# Componentes.net
KiCad netlist of a schematic drawn in Altium Designer
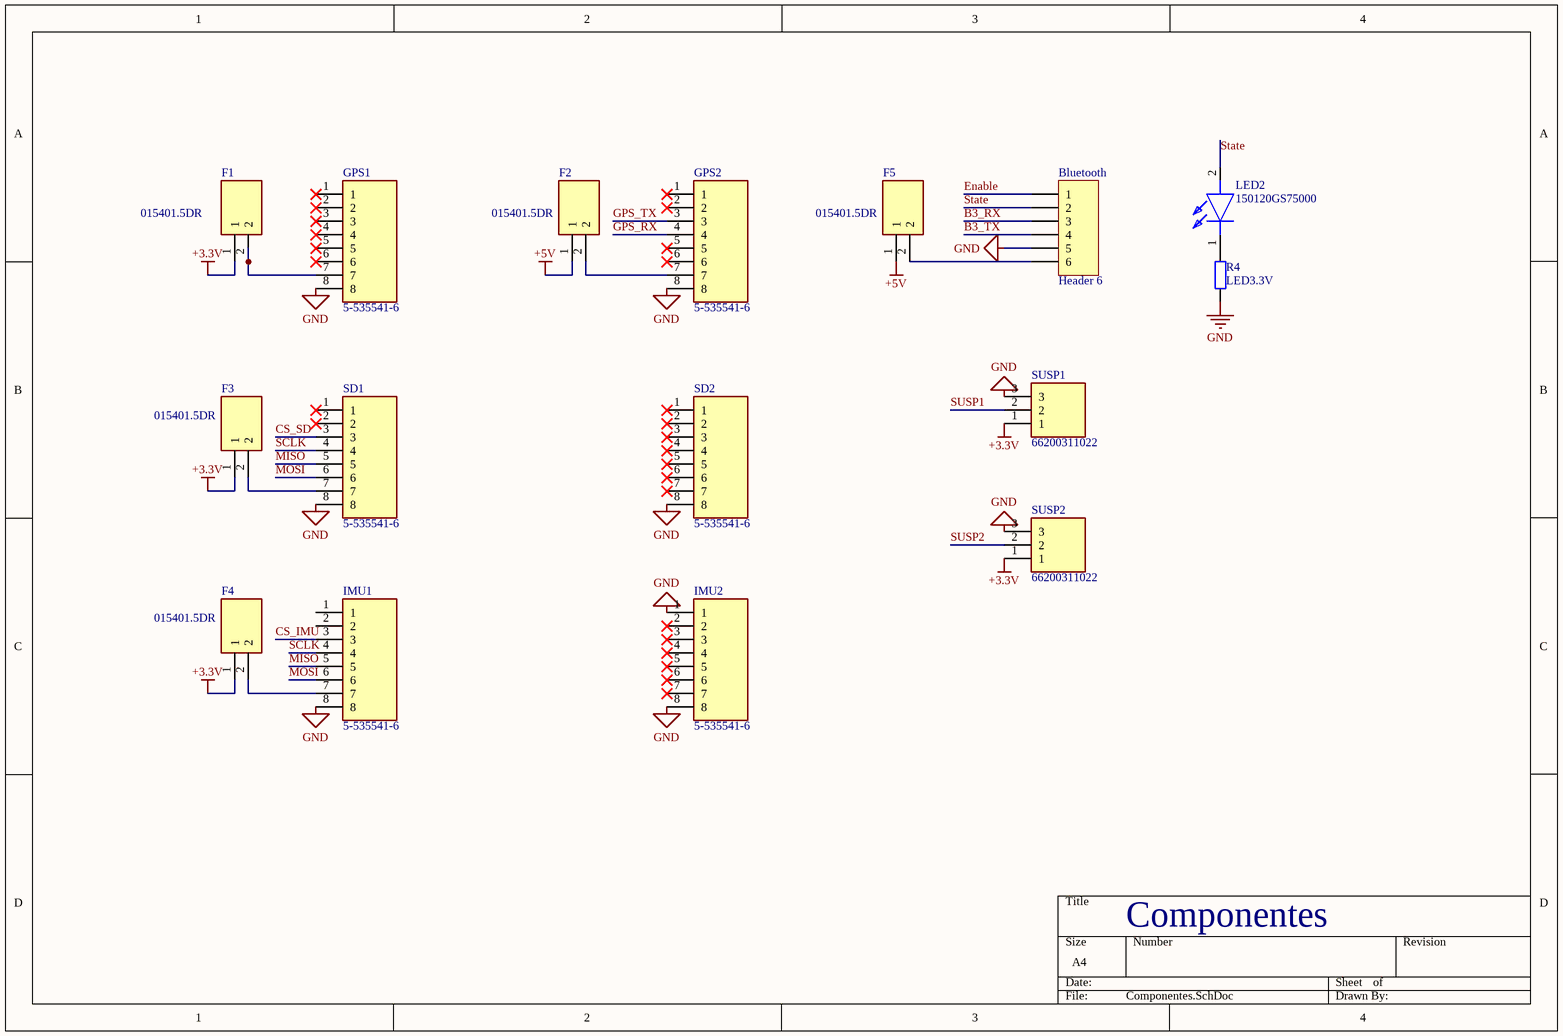
[diagram p0: Componentes.SchDoc]

(export (version "E")
  (design (tool "Eeschema 10.0.6"))
  (components
    (comp (ref "Bluetooth")
      (value "Header 6")
      (footprint "HDR1X6")
      (description "Header, 6-Pin")
      (fields (field (name "PUBLISHER") "Altium Limited"))
      (libsource (lib "Miscellaneous Connectors") (part "Header 6"))
    )
    (comp (ref "F1")
      (value "015401.5DR")
      (footprint "Fuse Holder")
      (description "Fuse")
      (fields (field (name "MOUSER PART NUMBER") "576-015401.5DR") (field (name "RS PART NUMBER") "7382879P"))
      (libsource (lib "BilbiotecaV2") (part "015401.5DR"))
    )
    (comp (ref "F2")
      (value "015401.5DR")
      (footprint "Fuse Holder")
      (description "Fuse")
      (fields (field (name "MOUSER PART NUMBER") "576-015401.5DR") (field (name "RS PART NUMBER") "7382879P"))
      (libsource (lib "TelemetriaV2") (part "015401.5DR"))
    )
    (comp (ref "F3")
      (value "015401.5DR")
      (footprint "Fuse Holder")
      (description "Fuse")
      (fields (field (name "MOUSER PART NUMBER") "576-015401.5DR") (field (name "RS PART NUMBER") "7382879P"))
      (libsource (lib "TelemetriaV2") (part "015401.5DR"))
    )
    (comp (ref "F4")
      (value "015401.5DR")
      (footprint "Fuse Holder")
      (description "Fuse")
      (fields (field (name "MOUSER PART NUMBER") "576-015401.5DR") (field (name "RS PART NUMBER") "7382879P"))
      (libsource (lib "TelemetriaV2") (part "015401.5DR"))
    )
    (comp (ref "F5")
      (value "015401.5DR")
      (footprint "Fuse Holder")
      (description "Fuse")
      (fields (field (name "MOUSER PART NUMBER") "576-015401.5DR") (field (name "RS PART NUMBER") "7382879P"))
      (libsource (lib "TelemetriaV2") (part "015401.5DR"))
    )
    (comp (ref "GPS1")
      (value "5-535541-6")
      (footprint "RHDR8W60P0X254_1X8_2082X250X850P")
      (description "Connector Socket Strip RCP 8 POS 2.54mm Solder ST Thru-Hole Gang of Tubes")
      (fields (field (name "MF") "TE Connectivity"))
      (libsource (lib "TelemetriaV2") (part "5-535541-6"))
    )
    (comp (ref "GPS2")
      (value "5-535541-6")
      (footprint "RHDR8W60P0X254_1X8_2082X250X850P")
      (description "Connector Socket Strip RCP 8 POS 2.54mm Solder ST Thru-Hole Gang of Tubes")
      (fields (field (name "MF") "TE Connectivity"))
      (libsource (lib "TelemetriaV2") (part "5-535541-6"))
    )
    (comp (ref "IMU1")
      (value "5-535541-6")
      (footprint "RHDR8W60P0X254_1X8_2082X250X850P")
      (description "Connector Socket Strip RCP 8 POS 2.54mm Solder ST Thru-Hole Gang of Tubes")
      (fields (field (name "MF") "TE Connectivity"))
      (libsource (lib "TelemetriaV2") (part "5-535541-6"))
    )
    (comp (ref "IMU2")
      (value "5-535541-6")
      (footprint "RHDR8W60P0X254_1X8_2082X250X850P")
      (description "Connector Socket Strip RCP 8 POS 2.54mm Solder ST Thru-Hole Gang of Tubes")
      (fields (field (name "MF") "TE Connectivity"))
      (libsource (lib "TelemetriaV2") (part "5-535541-6"))
    )
    (comp (ref "LED2")
      (value "150120GS75000")
      (footprint "SamacSys:LEDC3214X78N")
      (description "LED")
      (fields (field (name "MOUSER PART NUMBER") "710-150120GS75000"))
      (libsource (lib "*") (part "150120GS75000"))
    )
    (comp (ref "R4")
      (value "LED3.3V")
      (footprint "R 0805")
      (description "WRIS-KSKE SMT Thick Film Resistor, size 0805, 1Ohm, 0.33W")
      (fields
        (field (name "MANUFACTURER") "Wurth Elektronik")
        (field (name "MANUFACTURER PART NUMBER") "560050320011")
      )
      (libsource (lib "TelemetriaV2") (part "560050320011_2"))
    )
    (comp (ref "SD1")
      (value "5-535541-6")
      (footprint "RHDR8W60P0X254_1X8_2082X250X850P")
      (description "Connector Socket Strip RCP 8 POS 2.54mm Solder ST Thru-Hole Gang of Tubes")
      (fields (field (name "MF") "TE Connectivity"))
      (libsource (lib "TelemetriaV2") (part "5-535541-6"))
    )
    (comp (ref "SD2")
      (value "5-535541-6")
      (footprint "RHDR8W60P0X254_1X8_2082X250X850P")
      (description "Connector Socket Strip RCP 8 POS 2.54mm Solder ST Thru-Hole Gang of Tubes")
      (fields (field (name "MF") "TE Connectivity"))
      (libsource (lib "TelemetriaV2") (part "5-535541-6"))
    )
    (comp (ref "SUSP1")
      (value "66200311022")
      (footprint "SamacSys:66200311022")
      (description "Connector")
      (fields (field (name "MOUSER PART NUMBER") "710-66200311022"))
      (libsource (lib "*") (part "66200311022"))
    )
    (comp (ref "SUSP2")
      (value "66200311022")
      (footprint "SamacSys:66200311022")
      (description "Connector")
      (fields (field (name "MOUSER PART NUMBER") "710-66200311022"))
      (libsource (lib "*") (part "66200311022"))
    )
  )
  (nets
    (net (code "1") (name "+3.3V") (class "Default")
      (node (ref "F1") (pin "1") (pinfunction "1_1") (pintype "passive"))
      (node (ref "F3") (pin "1") (pinfunction "1_1") (pintype "passive"))
      (node (ref "F4") (pin "1") (pinfunction "1_1") (pintype "passive"))
      (node (ref "SUSP1") (pin "1") (pinfunction "1_1") (pintype "passive"))
      (node (ref "SUSP2") (pin "1") (pinfunction "1_1") (pintype "passive"))
    )
    (net (code "2") (name "+5V") (class "Default")
      (node (ref "F2") (pin "1") (pinfunction "1_1") (pintype "passive"))
      (node (ref "F5") (pin "1") (pinfunction "1_1") (pintype "passive"))
    )
    (net (code "3") (name "/B3_RX") (class "Default")
      (node (ref "Bluetooth") (pin "3") (pinfunction "3_3") (pintype "passive"))
    )
    (net (code "4") (name "/B3_TX") (class "Default")
      (node (ref "Bluetooth") (pin "4") (pinfunction "4_4") (pintype "passive"))
    )
    (net (code "5") (name "/CS_IMU") (class "Default")
      (node (ref "IMU1") (pin "3") (pinfunction "3_3") (pintype "passive"))
    )
    (net (code "6") (name "/CS_SD") (class "Default")
      (node (ref "SD1") (pin "3") (pinfunction "3_3") (pintype "passive"))
    )
    (net (code "7") (name "/Enable") (class "Default")
      (node (ref "Bluetooth") (pin "1") (pinfunction "1_1") (pintype "passive"))
    )
    (net (code "8") (name "/GPS_RX") (class "Default")
      (node (ref "GPS2") (pin "4") (pinfunction "4_4") (pintype "passive"))
    )
    (net (code "9") (name "/GPS_TX") (class "Default")
      (node (ref "GPS2") (pin "3") (pinfunction "3_3") (pintype "passive"))
    )
    (net (code "10") (name "/MISO") (class "Default")
      (node (ref "IMU1") (pin "5") (pinfunction "5_5") (pintype "passive"))
      (node (ref "SD1") (pin "5") (pinfunction "5_5") (pintype "passive"))
    )
    (net (code "11") (name "/MOSI") (class "Default")
      (node (ref "IMU1") (pin "6") (pinfunction "6_6") (pintype "passive"))
      (node (ref "SD1") (pin "6") (pinfunction "6_6") (pintype "passive"))
    )
    (net (code "12") (name "/SCLK") (class "Default")
      (node (ref "IMU1") (pin "4") (pinfunction "4_4") (pintype "passive"))
      (node (ref "SD1") (pin "4") (pinfunction "4_4") (pintype "passive"))
    )
    (net (code "13") (name "/SUSP1") (class "Default")
      (node (ref "SUSP1") (pin "2") (pinfunction "2_2") (pintype "passive"))
    )
    (net (code "14") (name "/SUSP2") (class "Default")
      (node (ref "SUSP2") (pin "2") (pinfunction "2_2") (pintype "passive"))
    )
    (net (code "15") (name "/State") (class "Default")
      (node (ref "Bluetooth") (pin "2") (pinfunction "2_2") (pintype "passive"))
      (node (ref "LED2") (pin "2") (pinfunction "A_2") (pintype "passive"))
    )
    (net (code "16") (name "GND") (class "Default")
      (node (ref "Bluetooth") (pin "5") (pinfunction "5_5") (pintype "passive"))
      (node (ref "GPS1") (pin "8") (pinfunction "8_8") (pintype "passive"))
      (node (ref "GPS2") (pin "8") (pinfunction "8_8") (pintype "passive"))
      (node (ref "IMU1") (pin "8") (pinfunction "8_8") (pintype "passive"))
      (node (ref "IMU2") (pin "1") (pinfunction "1_1") (pintype "passive"))
      (node (ref "IMU2") (pin "8") (pinfunction "8_8") (pintype "passive"))
      (node (ref "R4") (pin "1") (pinfunction "1_1") (pintype "passive"))
      (node (ref "SD1") (pin "8") (pinfunction "8_8") (pintype "passive"))
      (node (ref "SD2") (pin "8") (pinfunction "8_8") (pintype "passive"))
      (node (ref "SUSP1") (pin "3") (pinfunction "3_3") (pintype "passive"))
      (node (ref "SUSP2") (pin "3") (pinfunction "3_3") (pintype "passive"))
    )
    (net (code "17") (name "Net-(Bluetooth-Pad6)") (class "Default")
      (node (ref "Bluetooth") (pin "6") (pinfunction "6_6") (pintype "passive"))
      (node (ref "F5") (pin "2") (pinfunction "2_2") (pintype "passive"))
    )
    (net (code "18") (name "Net-(F1-Pad2)") (class "Default")
      (node (ref "F1") (pin "2") (pinfunction "2_2") (pintype "passive"))
      (node (ref "GPS1") (pin "7") (pinfunction "7_7") (pintype "passive"))
    )
    (net (code "19") (name "Net-(F2-Pad2)") (class "Default")
      (node (ref "F2") (pin "2") (pinfunction "2_2") (pintype "passive"))
      (node (ref "GPS2") (pin "7") (pinfunction "7_7") (pintype "passive"))
    )
    (net (code "20") (name "Net-(F3-Pad2)") (class "Default")
      (node (ref "F3") (pin "2") (pinfunction "2_2") (pintype "passive"))
      (node (ref "SD1") (pin "7") (pinfunction "7_7") (pintype "passive"))
    )
    (net (code "21") (name "Net-(F4-Pad2)") (class "Default")
      (node (ref "F4") (pin "2") (pinfunction "2_2") (pintype "passive"))
      (node (ref "IMU1") (pin "7") (pinfunction "7_7") (pintype "passive"))
    )
    (net (code "22") (name "Net-(LED2-K)") (class "Default")
      (node (ref "LED2") (pin "1") (pinfunction "K_1") (pintype "passive"))
      (node (ref "R4") (pin "2") (pinfunction "2_2") (pintype "passive"))
    )
    (net (code "23") (name "unconnected-(GPS1-Pad1)") (class "Default")
      (node (ref "GPS1") (pin "1") (pinfunction "1_1") (pintype "passive+no_connect"))
    )
    (net (code "24") (name "unconnected-(GPS1-Pad2)") (class "Default")
      (node (ref "GPS1") (pin "2") (pinfunction "2_2") (pintype "passive+no_connect"))
    )
    (net (code "25") (name "unconnected-(GPS1-Pad3)") (class "Default")
      (node (ref "GPS1") (pin "3") (pinfunction "3_3") (pintype "passive+no_connect"))
    )
    (net (code "26") (name "unconnected-(GPS1-Pad4)") (class "Default")
      (node (ref "GPS1") (pin "4") (pinfunction "4_4") (pintype "passive+no_connect"))
    )
    (net (code "27") (name "unconnected-(GPS1-Pad5)") (class "Default")
      (node (ref "GPS1") (pin "5") (pinfunction "5_5") (pintype "passive+no_connect"))
    )
    (net (code "28") (name "unconnected-(GPS1-Pad6)") (class "Default")
      (node (ref "GPS1") (pin "6") (pinfunction "6_6") (pintype "passive+no_connect"))
    )
    (net (code "29") (name "unconnected-(GPS2-Pad1)") (class "Default")
      (node (ref "GPS2") (pin "1") (pinfunction "1_1") (pintype "passive+no_connect"))
    )
    (net (code "30") (name "unconnected-(GPS2-Pad2)") (class "Default")
      (node (ref "GPS2") (pin "2") (pinfunction "2_2") (pintype "passive+no_connect"))
    )
    (net (code "31") (name "unconnected-(GPS2-Pad5)") (class "Default")
      (node (ref "GPS2") (pin "5") (pinfunction "5_5") (pintype "passive+no_connect"))
    )
    (net (code "32") (name "unconnected-(GPS2-Pad6)") (class "Default")
      (node (ref "GPS2") (pin "6") (pinfunction "6_6") (pintype "passive+no_connect"))
    )
    (net (code "33") (name "unconnected-(IMU1-Pad1)") (class "Default")
      (node (ref "IMU1") (pin "1") (pinfunction "1_1") (pintype "passive"))
    )
    (net (code "34") (name "unconnected-(IMU1-Pad2)") (class "Default")
      (node (ref "IMU1") (pin "2") (pinfunction "2_2") (pintype "passive"))
    )
    (net (code "35") (name "unconnected-(IMU2-Pad2)") (class "Default")
      (node (ref "IMU2") (pin "2") (pinfunction "2_2") (pintype "passive+no_connect"))
    )
    (net (code "36") (name "unconnected-(IMU2-Pad3)") (class "Default")
      (node (ref "IMU2") (pin "3") (pinfunction "3_3") (pintype "passive+no_connect"))
    )
    (net (code "37") (name "unconnected-(IMU2-Pad4)") (class "Default")
      (node (ref "IMU2") (pin "4") (pinfunction "4_4") (pintype "passive+no_connect"))
    )
    (net (code "38") (name "unconnected-(IMU2-Pad5)") (class "Default")
      (node (ref "IMU2") (pin "5") (pinfunction "5_5") (pintype "passive+no_connect"))
    )
    (net (code "39") (name "unconnected-(IMU2-Pad6)") (class "Default")
      (node (ref "IMU2") (pin "6") (pinfunction "6_6") (pintype "passive+no_connect"))
    )
    (net (code "40") (name "unconnected-(IMU2-Pad7)") (class "Default")
      (node (ref "IMU2") (pin "7") (pinfunction "7_7") (pintype "passive+no_connect"))
    )
    (net (code "41") (name "unconnected-(SD1-Pad1)") (class "Default")
      (node (ref "SD1") (pin "1") (pinfunction "1_1") (pintype "passive+no_connect"))
    )
    (net (code "42") (name "unconnected-(SD1-Pad2)") (class "Default")
      (node (ref "SD1") (pin "2") (pinfunction "2_2") (pintype "passive+no_connect"))
    )
    (net (code "43") (name "unconnected-(SD2-Pad1)") (class "Default")
      (node (ref "SD2") (pin "1") (pinfunction "1_1") (pintype "passive+no_connect"))
    )
    (net (code "44") (name "unconnected-(SD2-Pad2)") (class "Default")
      (node (ref "SD2") (pin "2") (pinfunction "2_2") (pintype "passive+no_connect"))
    )
    (net (code "45") (name "unconnected-(SD2-Pad3)") (class "Default")
      (node (ref "SD2") (pin "3") (pinfunction "3_3") (pintype "passive+no_connect"))
    )
    (net (code "46") (name "unconnected-(SD2-Pad4)") (class "Default")
      (node (ref "SD2") (pin "4") (pinfunction "4_4") (pintype "passive+no_connect"))
    )
    (net (code "47") (name "unconnected-(SD2-Pad5)") (class "Default")
      (node (ref "SD2") (pin "5") (pinfunction "5_5") (pintype "passive+no_connect"))
    )
    (net (code "48") (name "unconnected-(SD2-Pad6)") (class "Default")
      (node (ref "SD2") (pin "6") (pinfunction "6_6") (pintype "passive+no_connect"))
    )
    (net (code "49") (name "unconnected-(SD2-Pad7)") (class "Default")
      (node (ref "SD2") (pin "7") (pinfunction "7_7") (pintype "passive+no_connect"))
    )
  )
)
